# 7_Channel_Mixer.net
KiCad netlist of a schematic drawn in EAGLE
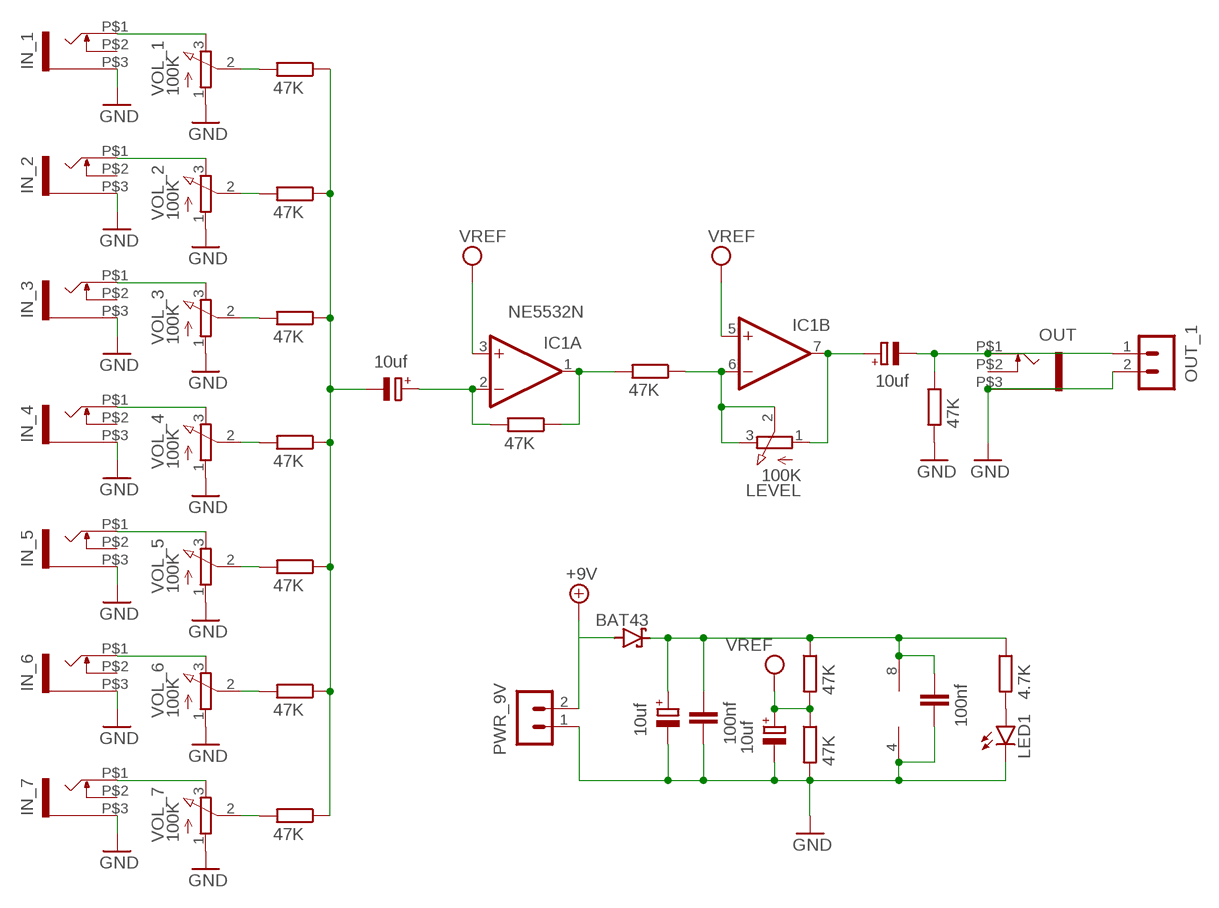
[diagram p0: schematic, sheet 1]

(export (version "E")
  (design (tool "Eeschema 10.0.6"))
  (components
    (comp (ref "C1")
      (value "10uf")
      (footprint "eagle-import:E2,5-6E")
      (libsource (lib "eagle-import") (part "CPOL-EUE2,5-6E"))
    )
    (comp (ref "C2")
      (value "10uf")
      (footprint "eagle-import:E2,5-6E")
      (libsource (lib "eagle-import") (part "CPOL-EUE2,5-6E"))
    )
    (comp (ref "C3")
      (value "10uf")
      (footprint "eagle-import:E2,5-6E")
      (libsource (lib "eagle-import") (part "CPOL-EUE2,5-6E"))
    )
    (comp (ref "C4")
      (value "10uf")
      (footprint "eagle-import:E2,5-6E")
      (libsource (lib "eagle-import") (part "CPOL-EUE2,5-6E"))
    )
    (comp (ref "C5")
      (value "100nf")
      (footprint "eagle-import:C050-024X044")
      (libsource (lib "eagle-import") (part "C-EU050-024X044"))
    )
    (comp (ref "C6")
      (value "100nf")
      (footprint "eagle-import:C050-024X044")
      (libsource (lib "eagle-import") (part "C-EU050-024X044"))
    )
    (comp (ref "D4")
      (value "BAT43")
      (footprint "eagle-import:DO35-10")
      (libsource (lib "eagle-import") (part "BAT42"))
    )
    (comp (ref "IC1")
      (value "NE5532N")
      (footprint "eagle-import:DIL08")
      (libsource (lib "eagle-import") (part "NE5532N"))
    )
    (comp (ref "IN_1")
      (value "WQP-PJ301M-12_JACK")
      (footprint "eagle-import:WQP-PJ301M-12_JACK")
      (libsource (lib "eagle-import") (part "WQP-PJ301M-12_JACK"))
    )
    (comp (ref "IN_2")
      (value "WQP-PJ301M-12_JACK")
      (footprint "eagle-import:WQP-PJ301M-12_JACK")
      (libsource (lib "eagle-import") (part "WQP-PJ301M-12_JACK"))
    )
    (comp (ref "IN_3")
      (value "WQP-PJ301M-12_JACK")
      (footprint "eagle-import:WQP-PJ301M-12_JACK")
      (libsource (lib "eagle-import") (part "WQP-PJ301M-12_JACK"))
    )
    (comp (ref "IN_4")
      (value "WQP-PJ301M-12_JACK")
      (footprint "eagle-import:WQP-PJ301M-12_JACK")
      (libsource (lib "eagle-import") (part "WQP-PJ301M-12_JACK"))
    )
    (comp (ref "IN_5")
      (value "WQP-PJ301M-12_JACK")
      (footprint "eagle-import:WQP-PJ301M-12_JACK")
      (libsource (lib "eagle-import") (part "WQP-PJ301M-12_JACK"))
    )
    (comp (ref "IN_6")
      (value "WQP-PJ301M-12_JACK")
      (footprint "eagle-import:WQP-PJ301M-12_JACK")
      (libsource (lib "eagle-import") (part "WQP-PJ301M-12_JACK"))
    )
    (comp (ref "IN_7")
      (value "WQP-PJ301M-12_JACK")
      (footprint "eagle-import:WQP-PJ301M-12_JACK")
      (libsource (lib "eagle-import") (part "WQP-PJ301M-12_JACK"))
    )
    (comp (ref "LED1")
      (value "LED3MM")
      (footprint "eagle-import:LED3MM")
      (libsource (lib "eagle-import") (part "LED3MM"))
    )
    (comp (ref "LEVEL")
      (value "100K")
      (footprint "eagle-import:EVUFXM")
      (libsource (lib "eagle-import") (part "EVUMF2"))
    )
    (comp (ref "OUT")
      (value "WQP-PJ301M-12_JACK")
      (footprint "eagle-import:WQP-PJ301M-12_JACK")
      (libsource (lib "eagle-import") (part "WQP-PJ301M-12_JACK"))
    )
    (comp (ref "OUT_1")
      (value "B2B-PH-K-S")
      (footprint "eagle-import:B2B-PH-K-S")
      (libsource (lib "eagle-import") (part "B2B-PH-K-S"))
    )
    (comp (ref "PWR_9V")
      (value "B2B-PH-K-S")
      (footprint "eagle-import:B2B-PH-K-S")
      (libsource (lib "eagle-import") (part "B2B-PH-K-S"))
    )
    (comp (ref "R1")
      (value "47K")
      (footprint "eagle-import:0204_7")
      (libsource (lib "eagle-import") (part "R-EU_0204/7"))
    )
    (comp (ref "R2")
      (value "47K")
      (footprint "eagle-import:0204_7")
      (libsource (lib "eagle-import") (part "R-EU_0204/7"))
    )
    (comp (ref "R3")
      (value "47K")
      (footprint "eagle-import:0204_7")
      (libsource (lib "eagle-import") (part "R-EU_0204/7"))
    )
    (comp (ref "R4")
      (value "47K")
      (footprint "eagle-import:0204_7")
      (libsource (lib "eagle-import") (part "R-EU_0204/7"))
    )
    (comp (ref "R5")
      (value "47K")
      (footprint "eagle-import:0204_7")
      (libsource (lib "eagle-import") (part "R-EU_0204/7"))
    )
    (comp (ref "R6")
      (value "47K")
      (footprint "eagle-import:0204_7")
      (libsource (lib "eagle-import") (part "R-EU_0204/7"))
    )
    (comp (ref "R7")
      (value "47K")
      (footprint "eagle-import:0204_7")
      (libsource (lib "eagle-import") (part "R-EU_0204/7"))
    )
    (comp (ref "R8")
      (value "47K")
      (footprint "eagle-import:0204_7")
      (libsource (lib "eagle-import") (part "R-EU_0204/7"))
    )
    (comp (ref "R9")
      (value "47K")
      (footprint "eagle-import:0204_7")
      (libsource (lib "eagle-import") (part "R-EU_0204/7"))
    )
    (comp (ref "R10")
      (value "47K")
      (footprint "eagle-import:0204_7")
      (libsource (lib "eagle-import") (part "R-EU_0204/7"))
    )
    (comp (ref "R11")
      (value "47K")
      (footprint "eagle-import:0204_7")
      (libsource (lib "eagle-import") (part "R-EU_0204/7"))
    )
    (comp (ref "R12")
      (value "4.7K")
      (footprint "eagle-import:0204_7")
      (libsource (lib "eagle-import") (part "R-EU_0204/7"))
    )
    (comp (ref "R13")
      (value "47K")
      (footprint "eagle-import:0204_7")
      (libsource (lib "eagle-import") (part "R-EU_0204/7"))
    )
    (comp (ref "VOL_1")
      (value "100K")
      (footprint "eagle-import:EVUFXM")
      (libsource (lib "eagle-import") (part "EVUMF2"))
    )
    (comp (ref "VOL_2")
      (value "100K")
      (footprint "eagle-import:EVUFXM")
      (libsource (lib "eagle-import") (part "EVUMF2"))
    )
    (comp (ref "VOL_3")
      (value "100K")
      (footprint "eagle-import:EVUFXM")
      (libsource (lib "eagle-import") (part "EVUMF2"))
    )
    (comp (ref "VOL_4")
      (value "100K")
      (footprint "eagle-import:EVUFXM")
      (libsource (lib "eagle-import") (part "EVUMF2"))
    )
    (comp (ref "VOL_5")
      (value "100K")
      (footprint "eagle-import:EVUFXM")
      (libsource (lib "eagle-import") (part "EVUMF2"))
    )
    (comp (ref "VOL_6")
      (value "100K")
      (footprint "eagle-import:EVUFXM")
      (libsource (lib "eagle-import") (part "EVUMF2"))
    )
    (comp (ref "VOL_7")
      (value "100K")
      (footprint "eagle-import:EVUFXM")
      (libsource (lib "eagle-import") (part "EVUMF2"))
    )
  )
  (nets
    (net (code "1") (name "+9V") (class "Default")
      (node (ref "D4") (pin "A") (pinfunction "A_A") (pintype "passive"))
      (node (ref "PWR_9V") (pin "2") (pinfunction "2_2") (pintype "passive"))
    )
    (net (code "2") (name "GND") (class "Default")
      (node (ref "C3") (pin "-") (pinfunction "-_-") (pintype "passive"))
      (node (ref "C4") (pin "-") (pinfunction "-_-") (pintype "passive"))
      (node (ref "C5") (pin "1") (pinfunction "1_1") (pintype "passive"))
      (node (ref "C6") (pin "1") (pinfunction "1_1") (pintype "passive"))
      (node (ref "IC1") (pin "4") (pinfunction "V-_4") (pintype "power_in"))
      (node (ref "IN_1") (pin "P$3") (pinfunction "1_P$3") (pintype "passive"))
      (node (ref "IN_2") (pin "P$3") (pinfunction "1_P$3") (pintype "passive"))
      (node (ref "IN_3") (pin "P$3") (pinfunction "1_P$3") (pintype "passive"))
      (node (ref "IN_4") (pin "P$3") (pinfunction "1_P$3") (pintype "passive"))
      (node (ref "IN_5") (pin "P$3") (pinfunction "1_P$3") (pintype "passive"))
      (node (ref "IN_6") (pin "P$3") (pinfunction "1_P$3") (pintype "passive"))
      (node (ref "IN_7") (pin "P$3") (pinfunction "1_P$3") (pintype "passive"))
      (node (ref "LED1") (pin "K") (pinfunction "C_K") (pintype "passive"))
      (node (ref "OUT") (pin "P$3") (pinfunction "1_P$3") (pintype "passive"))
      (node (ref "OUT_1") (pin "2") (pinfunction "2_2") (pintype "passive"))
      (node (ref "PWR_9V") (pin "1") (pinfunction "1_1") (pintype "passive"))
      (node (ref "R11") (pin "2") (pinfunction "2_2") (pintype "passive"))
      (node (ref "R9") (pin "2") (pinfunction "2_2") (pintype "passive"))
      (node (ref "VOL_1") (pin "1") (pinfunction "A_1") (pintype "passive"))
      (node (ref "VOL_2") (pin "1") (pinfunction "A_1") (pintype "passive"))
      (node (ref "VOL_3") (pin "1") (pinfunction "A_1") (pintype "passive"))
      (node (ref "VOL_4") (pin "1") (pinfunction "A_1") (pintype "passive"))
      (node (ref "VOL_5") (pin "1") (pinfunction "A_1") (pintype "passive"))
      (node (ref "VOL_6") (pin "1") (pinfunction "A_1") (pintype "passive"))
      (node (ref "VOL_7") (pin "1") (pinfunction "A_1") (pintype "passive"))
    )
    (net (code "3") (name "Net-(C1-Pad-)") (class "Default")
      (node (ref "C1") (pin "-") (pinfunction "-_-") (pintype "passive"))
      (node (ref "R1") (pin "1") (pinfunction "1_1") (pintype "passive"))
      (node (ref "R13") (pin "1") (pinfunction "1_1") (pintype "passive"))
      (node (ref "R2") (pin "1") (pinfunction "1_1") (pintype "passive"))
      (node (ref "R3") (pin "1") (pinfunction "1_1") (pintype "passive"))
      (node (ref "R4") (pin "1") (pinfunction "1_1") (pintype "passive"))
      (node (ref "R5") (pin "1") (pinfunction "1_1") (pintype "passive"))
      (node (ref "R6") (pin "1") (pinfunction "1_1") (pintype "passive"))
    )
    (net (code "4") (name "Net-(IC1A--IN)") (class "Default")
      (node (ref "C1") (pin "+") (pinfunction "+_+") (pintype "passive"))
      (node (ref "IC1") (pin "2") (pinfunction "-IN_2") (pintype "input"))
      (node (ref "R7") (pin "2") (pinfunction "2_2") (pintype "passive"))
    )
    (net (code "5") (name "Net-(IC1A-OUT)") (class "Default")
      (node (ref "IC1") (pin "1") (pinfunction "OUT_1") (pintype "output"))
      (node (ref "R7") (pin "1") (pinfunction "1_1") (pintype "passive"))
      (node (ref "R8") (pin "2") (pinfunction "2_2") (pintype "passive"))
    )
    (net (code "6") (name "Net-(IC1B--IN)") (class "Default")
      (node (ref "IC1") (pin "6") (pinfunction "-IN_6") (pintype "input"))
      (node (ref "LEVEL") (pin "2") (pinfunction "S_2") (pintype "passive"))
      (node (ref "LEVEL") (pin "3") (pinfunction "E_3") (pintype "passive"))
      (node (ref "R8") (pin "1") (pinfunction "1_1") (pintype "passive"))
    )
    (net (code "7") (name "Net-(IC1B-OUT)") (class "Default")
      (node (ref "C2") (pin "+") (pinfunction "+_+") (pintype "passive"))
      (node (ref "IC1") (pin "7") (pinfunction "OUT_7") (pintype "output"))
      (node (ref "LEVEL") (pin "1") (pinfunction "A_1") (pintype "passive"))
    )
    (net (code "8") (name "Net-(IC1C-V+)") (class "Default")
      (node (ref "C4") (pin "+") (pinfunction "+_+") (pintype "passive"))
      (node (ref "C5") (pin "2") (pinfunction "2_2") (pintype "passive"))
      (node (ref "C6") (pin "2") (pinfunction "2_2") (pintype "passive"))
      (node (ref "D4") (pin "C") (pinfunction "C_C") (pintype "passive"))
      (node (ref "IC1") (pin "8") (pinfunction "V+_8") (pintype "power_in"))
      (node (ref "R10") (pin "1") (pinfunction "1_1") (pintype "passive"))
      (node (ref "R12") (pin "1") (pinfunction "1_1") (pintype "passive"))
    )
    (net (code "9") (name "Net-(IN_1-2)") (class "Default")
      (node (ref "IN_1") (pin "P$1") (pinfunction "2_P$1") (pintype "passive"))
      (node (ref "VOL_1") (pin "3") (pinfunction "E_3") (pintype "passive"))
    )
    (net (code "10") (name "Net-(IN_2-2)") (class "Default")
      (node (ref "IN_2") (pin "P$1") (pinfunction "2_P$1") (pintype "passive"))
      (node (ref "VOL_2") (pin "3") (pinfunction "E_3") (pintype "passive"))
    )
    (net (code "11") (name "Net-(IN_3-2)") (class "Default")
      (node (ref "IN_3") (pin "P$1") (pinfunction "2_P$1") (pintype "passive"))
      (node (ref "VOL_3") (pin "3") (pinfunction "E_3") (pintype "passive"))
    )
    (net (code "12") (name "Net-(IN_4-2)") (class "Default")
      (node (ref "IN_4") (pin "P$1") (pinfunction "2_P$1") (pintype "passive"))
      (node (ref "VOL_4") (pin "3") (pinfunction "E_3") (pintype "passive"))
    )
    (net (code "13") (name "Net-(IN_5-2)") (class "Default")
      (node (ref "IN_5") (pin "P$1") (pinfunction "2_P$1") (pintype "passive"))
      (node (ref "VOL_5") (pin "3") (pinfunction "E_3") (pintype "passive"))
    )
    (net (code "14") (name "Net-(IN_6-2)") (class "Default")
      (node (ref "IN_6") (pin "P$1") (pinfunction "2_P$1") (pintype "passive"))
      (node (ref "VOL_6") (pin "3") (pinfunction "E_3") (pintype "passive"))
    )
    (net (code "15") (name "Net-(IN_7-2)") (class "Default")
      (node (ref "IN_7") (pin "P$1") (pinfunction "2_P$1") (pintype "passive"))
      (node (ref "VOL_7") (pin "3") (pinfunction "E_3") (pintype "passive"))
    )
    (net (code "16") (name "Net-(LED1-PadA)") (class "Default")
      (node (ref "LED1") (pin "A") (pinfunction "A_A") (pintype "passive"))
      (node (ref "R12") (pin "2") (pinfunction "2_2") (pintype "passive"))
    )
    (net (code "17") (name "Net-(OUT-2)") (class "Default")
      (node (ref "C2") (pin "-") (pinfunction "-_-") (pintype "passive"))
      (node (ref "OUT") (pin "P$1") (pinfunction "2_P$1") (pintype "passive"))
      (node (ref "OUT_1") (pin "1") (pinfunction "1_1") (pintype "passive"))
      (node (ref "R9") (pin "1") (pinfunction "1_1") (pintype "passive"))
    )
    (net (code "18") (name "Net-(VOL_1-S)") (class "Default")
      (node (ref "R5") (pin "2") (pinfunction "2_2") (pintype "passive"))
      (node (ref "VOL_1") (pin "2") (pinfunction "S_2") (pintype "passive"))
    )
    (net (code "19") (name "Net-(VOL_2-S)") (class "Default")
      (node (ref "R1") (pin "2") (pinfunction "2_2") (pintype "passive"))
      (node (ref "VOL_2") (pin "2") (pinfunction "S_2") (pintype "passive"))
    )
    (net (code "20") (name "Net-(VOL_3-S)") (class "Default")
      (node (ref "R2") (pin "2") (pinfunction "2_2") (pintype "passive"))
      (node (ref "VOL_3") (pin "2") (pinfunction "S_2") (pintype "passive"))
    )
    (net (code "21") (name "Net-(VOL_4-S)") (class "Default")
      (node (ref "R3") (pin "2") (pinfunction "2_2") (pintype "passive"))
      (node (ref "VOL_4") (pin "2") (pinfunction "S_2") (pintype "passive"))
    )
    (net (code "22") (name "Net-(VOL_5-S)") (class "Default")
      (node (ref "R4") (pin "2") (pinfunction "2_2") (pintype "passive"))
      (node (ref "VOL_5") (pin "2") (pinfunction "S_2") (pintype "passive"))
    )
    (net (code "23") (name "Net-(VOL_6-S)") (class "Default")
      (node (ref "R6") (pin "2") (pinfunction "2_2") (pintype "passive"))
      (node (ref "VOL_6") (pin "2") (pinfunction "S_2") (pintype "passive"))
    )
    (net (code "24") (name "Net-(VOL_7-S)") (class "Default")
      (node (ref "R13") (pin "2") (pinfunction "2_2") (pintype "passive"))
      (node (ref "VOL_7") (pin "2") (pinfunction "S_2") (pintype "passive"))
    )
    (net (code "25") (name "VREF") (class "Default")
      (node (ref "C3") (pin "+") (pinfunction "+_+") (pintype "passive"))
      (node (ref "IC1") (pin "3") (pinfunction "+IN_3") (pintype "input"))
      (node (ref "IC1") (pin "5") (pinfunction "+IN_5") (pintype "input"))
      (node (ref "R10") (pin "2") (pinfunction "2_2") (pintype "passive"))
      (node (ref "R11") (pin "1") (pinfunction "1_1") (pintype "passive"))
    )
    (net (code "26") (name "unconnected-(IN_1-3-PadP$2)") (class "Default")
      (node (ref "IN_1") (pin "P$2") (pinfunction "3_P$2") (pintype "passive"))
    )
    (net (code "27") (name "unconnected-(IN_2-3-PadP$2)") (class "Default")
      (node (ref "IN_2") (pin "P$2") (pinfunction "3_P$2") (pintype "passive"))
    )
    (net (code "28") (name "unconnected-(IN_3-3-PadP$2)") (class "Default")
      (node (ref "IN_3") (pin "P$2") (pinfunction "3_P$2") (pintype "passive"))
    )
    (net (code "29") (name "unconnected-(IN_4-3-PadP$2)") (class "Default")
      (node (ref "IN_4") (pin "P$2") (pinfunction "3_P$2") (pintype "passive"))
    )
    (net (code "30") (name "unconnected-(IN_5-3-PadP$2)") (class "Default")
      (node (ref "IN_5") (pin "P$2") (pinfunction "3_P$2") (pintype "passive"))
    )
    (net (code "31") (name "unconnected-(IN_6-3-PadP$2)") (class "Default")
      (node (ref "IN_6") (pin "P$2") (pinfunction "3_P$2") (pintype "passive"))
    )
    (net (code "32") (name "unconnected-(IN_7-3-PadP$2)") (class "Default")
      (node (ref "IN_7") (pin "P$2") (pinfunction "3_P$2") (pintype "passive"))
    )
    (net (code "33") (name "unconnected-(OUT-3-PadP$2)") (class "Default")
      (node (ref "OUT") (pin "P$2") (pinfunction "3_P$2") (pintype "passive"))
    )
  )
)
